# Unidirectional_lvlshifter.net
KiCad netlist of a schematic drawn in Altium Designer
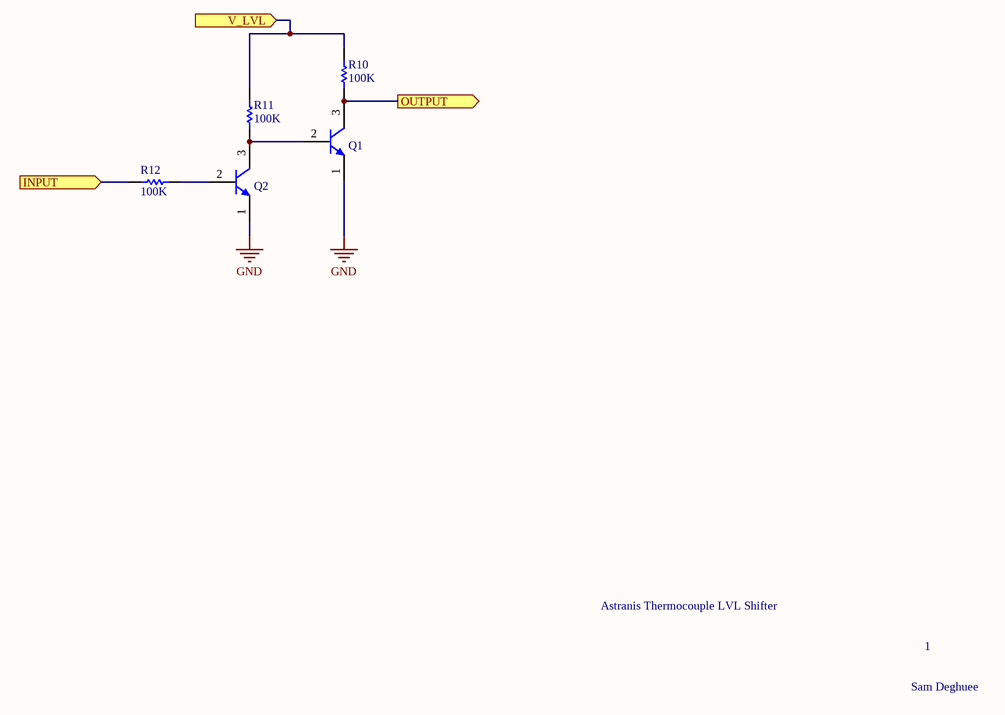
[diagram p0: Unidirectional_lvlshifter.SchDoc]

(export (version "E")
  (design (tool "Eeschema 10.0.6"))
  (components
    (comp (ref "Q1")
      (value "MPSA18G")
      (footprint "ONSC-TO-92-3-29-11")
      (description "Low Noise Transistor, NPN Silicon, 3-Pin TO-92, Pb-Free, Bulk Box")
      (fields (field (name "MANUFACTURER") "On Semiconductor"))
      (libsource (lib "Altium Content Vault") (part "ONSC-NPN-E1B2C3-3"))
    )
    (comp (ref "Q2")
      (value "MPSA18G")
      (footprint "ONSC-TO-92-3-29-11")
      (description "Low Noise Transistor, NPN Silicon, 3-Pin TO-92, Pb-Free, Bulk Box")
      (fields (field (name "MANUFACTURER") "On Semiconductor"))
      (libsource (lib "Altium Content Vault") (part "ONSC-NPN-E1B2C3-3"))
    )
    (comp (ref "R10")
      (value "100K")
      (footprint "RESC0603(1608)_L")
      (description "0603 (1608 Metric) Chip Resistor")
      (fields (field (name "Comment") "RES0603"))
      (libsource (lib "Altium Content Vault") (part "RES_3"))
    )
    (comp (ref "R11")
      (value "100K")
      (footprint "RESC0603(1608)_L")
      (description "0603 (1608 Metric) Chip Resistor")
      (fields (field (name "Comment") "RES0603"))
      (libsource (lib "Altium Content Vault") (part "RES_3"))
    )
    (comp (ref "R12")
      (value "100K")
      (footprint "RESC0603(1608)_L")
      (description "0603 (1608 Metric) Chip Resistor")
      (fields (field (name "Comment") "RES0603"))
      (libsource (lib "Altium Content Vault") (part "RES_3"))
    )
  )
  (nets
    (net (code "1") (name "/INPUT") (class "Default")
      (node (ref "R12") (pin "1") (pinfunction "1_1") (pintype "passive"))
    )
    (net (code "2") (name "/OUTPUT") (class "Default")
      (node (ref "Q1") (pin "3") (pinfunction "C_3") (pintype "passive"))
      (node (ref "R10") (pin "2") (pinfunction "2_2") (pintype "passive"))
    )
    (net (code "3") (name "/V_LVL") (class "Default")
      (node (ref "R10") (pin "1") (pinfunction "1_1") (pintype "passive"))
      (node (ref "R11") (pin "1") (pinfunction "1_1") (pintype "passive"))
    )
    (net (code "4") (name "GND") (class "Default")
      (node (ref "Q1") (pin "1") (pinfunction "E_1") (pintype "passive"))
      (node (ref "Q2") (pin "1") (pinfunction "E_1") (pintype "passive"))
    )
    (net (code "5") (name "Net-(Q1-B)") (class "Default")
      (node (ref "Q1") (pin "2") (pinfunction "B_2") (pintype "passive"))
      (node (ref "Q2") (pin "3") (pinfunction "C_3") (pintype "passive"))
      (node (ref "R11") (pin "2") (pinfunction "2_2") (pintype "passive"))
    )
    (net (code "6") (name "Net-(Q2-B)") (class "Default")
      (node (ref "Q2") (pin "2") (pinfunction "B_2") (pintype "passive"))
      (node (ref "R12") (pin "2") (pinfunction "2_2") (pintype "passive"))
    )
  )
)
